# main.net
KiCad netlist of a schematic drawn in Altium Designer
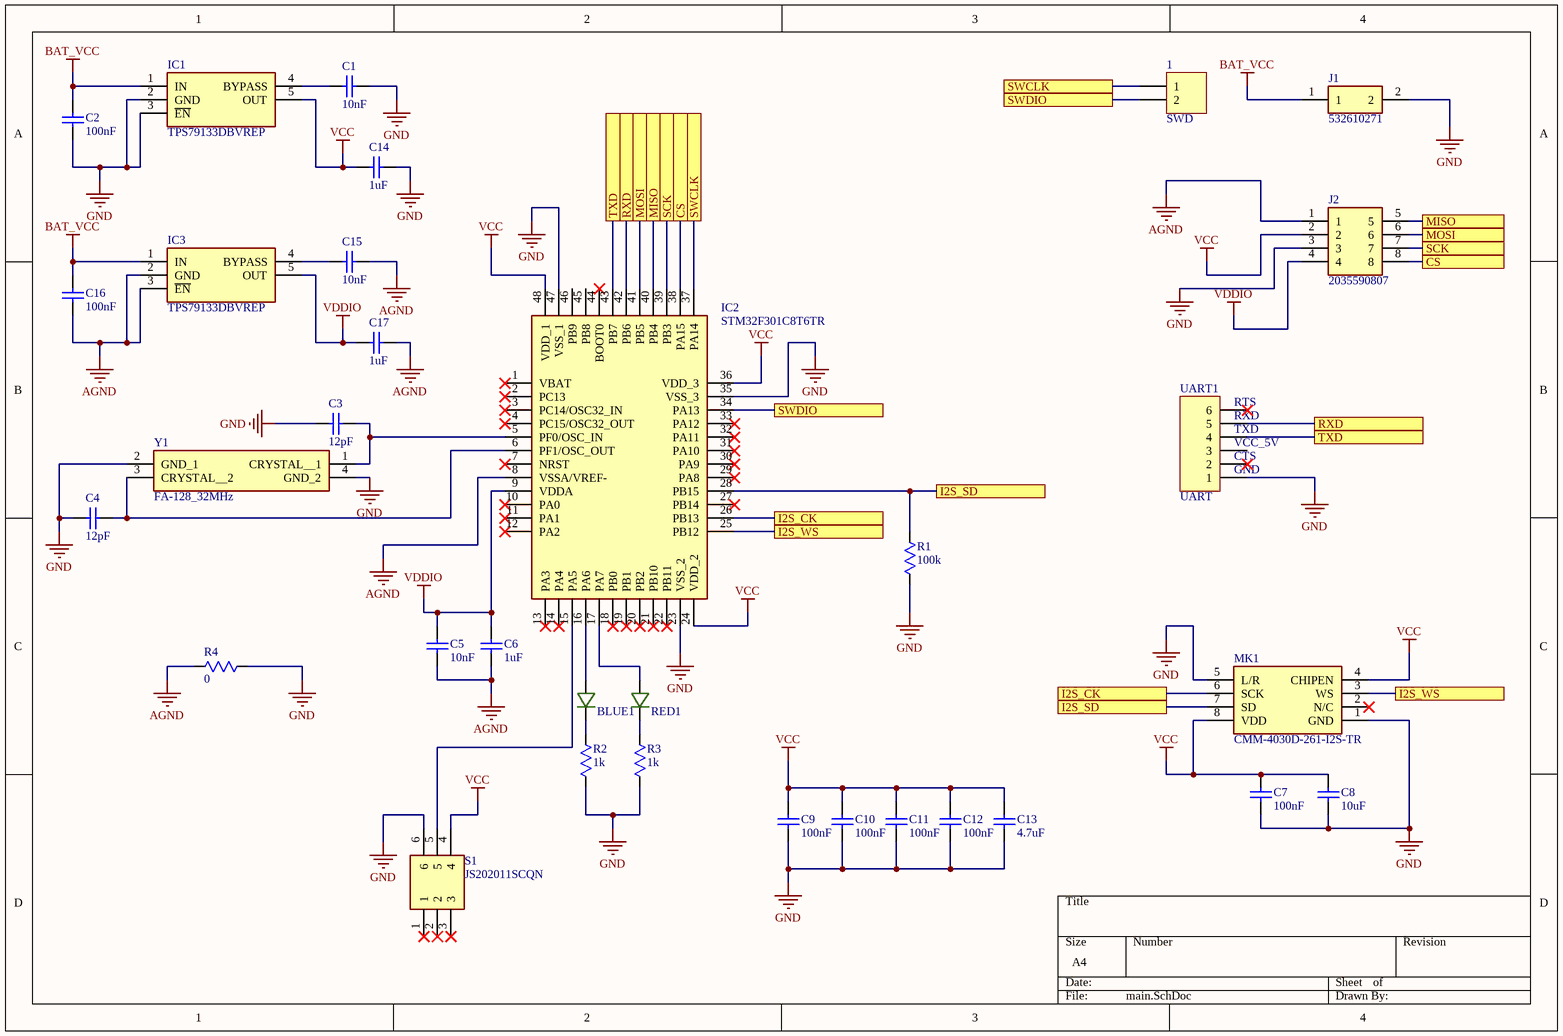
[diagram p0: main.SchDoc]

(export (version "E")
  (design (tool "Eeschema 10.0.6"))
  (components
    (comp (ref "1")
      (value "SWD")
      (footprint "HDR1X2")
      (description "Header, 2-Pin")
      (fields (field (name "PUBLISHER") "Altium Limited"))
      (libsource (lib "Miscellaneous Connectors") (part "Header 2"))
    )
    (comp (ref "BLUE1")
      (value "LG_L29K")
      (footprint "OSRAM LG L29K")
      (description "LED Uni-Color Green 572nm 2-Pin Chip 0603(1608Metric) T/R")
      (libsource (lib "Wearable components") (part "LG_L29K"))
    )
    (comp (ref "C1")
      (value "10nF")
      (footprint "CAP_2012")
      (description "2012(Metric) smd ceramic capacitor")
      (fields (field (name "TOLERANCE") "80%"))
      (libsource (lib "smd componenets") (part "CAP 2012"))
    )
    (comp (ref "C2")
      (value "100nF")
      (footprint "CAP_2012")
      (description "2012(Metric) smd ceramic capacitor")
      (fields (field (name "TOLERANCE") "80%"))
      (libsource (lib "smd componenets") (part "CAP 2012"))
    )
    (comp (ref "C3")
      (value "12pF")
      (footprint "CAP_2012")
      (description "2012(Metric) smd ceramic capacitor")
      (fields (field (name "TOLERANCE") "80%"))
      (libsource (lib "smd componenets") (part "CAP 2012"))
    )
    (comp (ref "C4")
      (value "12pF")
      (footprint "CAP_2012")
      (description "2012(Metric) smd ceramic capacitor")
      (fields (field (name "TOLERANCE") "80%"))
      (libsource (lib "smd componenets") (part "CAP 2012"))
    )
    (comp (ref "C5")
      (value "10nF")
      (footprint "CAP_2012")
      (description "2012(Metric) smd ceramic capacitor")
      (fields (field (name "TOLERANCE") "80%"))
      (libsource (lib "smd componenets") (part "CAP 2012"))
    )
    (comp (ref "C6")
      (value "1uF")
      (footprint "CAP_2012")
      (description "2012(Metric) smd ceramic capacitor")
      (fields (field (name "TOLERANCE") "80%"))
      (libsource (lib "smd componenets") (part "CAP 2012"))
    )
    (comp (ref "C7")
      (value "100nF")
      (footprint "CAP_2012")
      (description "2012(Metric) smd ceramic capacitor")
      (fields (field (name "TOLERANCE") "80%"))
      (libsource (lib "smd componenets") (part "CAP 2012"))
    )
    (comp (ref "C8")
      (value "10uF")
      (footprint "CAP_2012")
      (description "2012(Metric) smd ceramic capacitor")
      (fields (field (name "TOLERANCE") "80%"))
      (libsource (lib "smd componenets") (part "CAP 2012"))
    )
    (comp (ref "C9")
      (value "100nF")
      (footprint "CAP_2012")
      (description "2012(Metric) smd ceramic capacitor")
      (fields (field (name "TOLERANCE") "80%"))
      (libsource (lib "smd componenets") (part "CAP 2012"))
    )
    (comp (ref "C10")
      (value "100nF")
      (footprint "CAP_2012")
      (description "2012(Metric) smd ceramic capacitor")
      (fields (field (name "TOLERANCE") "80%"))
      (libsource (lib "smd componenets") (part "CAP 2012"))
    )
    (comp (ref "C11")
      (value "100nF")
      (footprint "CAP_2012")
      (description "2012(Metric) smd ceramic capacitor")
      (fields (field (name "TOLERANCE") "80%"))
      (libsource (lib "smd componenets") (part "CAP 2012"))
    )
    (comp (ref "C12")
      (value "100nF")
      (footprint "CAP_2012")
      (description "2012(Metric) smd ceramic capacitor")
      (fields (field (name "TOLERANCE") "80%"))
      (libsource (lib "smd componenets") (part "CAP 2012"))
    )
    (comp (ref "C13")
      (value "4.7uF")
      (footprint "CAP_2012")
      (description "2012(Metric) smd ceramic capacitor")
      (fields (field (name "TOLERANCE") "80%"))
      (libsource (lib "smd componenets") (part "CAP 2012"))
    )
    (comp (ref "C14")
      (value "1uF")
      (footprint "CAP_2012")
      (description "2012(Metric) smd ceramic capacitor")
      (fields (field (name "TOLERANCE") "80%"))
      (libsource (lib "smd componenets") (part "CAP 2012"))
    )
    (comp (ref "C15")
      (value "10nF")
      (footprint "CAP_2012")
      (description "2012(Metric) smd ceramic capacitor")
      (fields (field (name "TOLERANCE") "80%"))
      (libsource (lib "smd componenets") (part "CAP 2012"))
    )
    (comp (ref "C16")
      (value "100nF")
      (footprint "CAP_2012")
      (description "2012(Metric) smd ceramic capacitor")
      (fields (field (name "TOLERANCE") "80%"))
      (libsource (lib "smd componenets") (part "CAP 2012"))
    )
    (comp (ref "C17")
      (value "1uF")
      (footprint "CAP_2012")
      (description "2012(Metric) smd ceramic capacitor")
      (fields (field (name "TOLERANCE") "80%"))
      (libsource (lib "smd componenets") (part "CAP 2012"))
    )
    (comp (ref "IC1")
      (value "TPS79133DBVREP")
      (footprint "SamacSys:SOT95P280X145-5N")
      (description "Integrated Circuit")
      (fields (field (name "MOUSER PART NUMBER") "595-TPS79133DBVREP"))
      (libsource (lib "*") (part "TPS79133DBVREP"))
    )
    (comp (ref "IC2")
      (value "STM32F301C8T6TR")
      (footprint "SamacSys:QFP50P900X900X160-48N")
      (description "Integrated Circuit")
      (fields (field (name "MOUSER PART NUMBER") "511-STM32F301C8T6TR"))
      (libsource (lib "SamacSys") (part "STM32F301C8T6TR"))
    )
    (comp (ref "IC3")
      (value "TPS79133DBVREP")
      (footprint "SamacSys:SOT95P280X145-5N")
      (description "Integrated Circuit")
      (fields (field (name "MOUSER PART NUMBER") "595-TPS79133DBVREP"))
      (libsource (lib "*") (part "TPS79133DBVREP"))
    )
    (comp (ref "J1")
      (value "532610271")
      (footprint "SamacSys:532610271")
      (description "Connector")
      (libsource (lib "SamacSys") (part "532610271"))
    )
    (comp (ref "J2")
      (value "2035590807")
      (footprint "SamacSys:2035590807")
      (description "Connector")
      (libsource (lib "*") (part "2035590807"))
    )
    (comp (ref "MK1")
      (value "CMM-4030D-261-I2S-TR")
      (footprint "SamacSys:CMM4030D261I2STR")
      (description "Microphone")
      (fields (field (name "MOUSER PART NUMBER") "490-CMM4030D261I2STR"))
      (libsource (lib "SamacSys") (part "CMM-4030D-261-I2S-TR"))
    )
    (comp (ref "R1")
      (value "100k")
      (footprint "RES_2012")
      (description "2012(Metric) smd resistor")
      (fields
        (field (name "MANUFACTURER_PART_NUMBER") "WR08X000 PTL")
        (field (name "TOLERANCE") "1%")
        (field (name "COPYRIGHT") "Copyright (C) 2016 Accelerated Designs. All rights reserved")
      )
      (libsource (lib "smd componenets") (part "RES 2012"))
    )
    (comp (ref "R2")
      (value "1k")
      (footprint "RES_2012")
      (description "2012(Metric) smd resistor")
      (fields
        (field (name "MANUFACTURER_PART_NUMBER") "WR08X000 PTL")
        (field (name "TOLERANCE") "1%")
        (field (name "COPYRIGHT") "Copyright (C) 2016 Accelerated Designs. All rights reserved")
      )
      (libsource (lib "smd componenets") (part "RES 2012"))
    )
    (comp (ref "R3")
      (value "1k")
      (footprint "RES_2012")
      (description "2012(Metric) smd resistor")
      (fields
        (field (name "MANUFACTURER_PART_NUMBER") "WR08X000 PTL")
        (field (name "TOLERANCE") "1%")
        (field (name "COPYRIGHT") "Copyright (C) 2016 Accelerated Designs. All rights reserved")
      )
      (libsource (lib "smd componenets") (part "RES 2012"))
    )
    (comp (ref "R4")
      (value "0")
      (footprint "RES_2012")
      (description "2012(Metric) smd resistor")
      (fields
        (field (name "MANUFACTURER_PART_NUMBER") "WR08X000 PTL")
        (field (name "TOLERANCE") "1%")
        (field (name "COPYRIGHT") "Copyright (C) 2016 Accelerated Designs. All rights reserved")
      )
      (libsource (lib "smd componenets") (part "RES 2012"))
    )
    (comp (ref "RED1")
      (value "LG_L29K")
      (footprint "OSRAM LG L29K")
      (description "LED Uni-Color Green 572nm 2-Pin Chip 0603(1608Metric) T/R")
      (libsource (lib "Wearable components") (part "LG_L29K"))
    )
    (comp (ref "S1")
      (value "JS202011SCQN")
      (footprint "SamacSys:JS202011SCQN")
      (description "Switch")
      (fields (field (name "MOUSER PART NUMBER") "611-JS202011SCQN"))
      (libsource (lib "*") (part "JS202011SCQN"))
    )
    (comp (ref "UART1")
      (value "UART")
      (footprint "HDR1X6")
      (description "Header, 6-Pin")
      (fields (field (name "PUBLISHER") "Altium Limited"))
      (libsource (lib "Miscellaneous Connectors") (part "Header 6"))
    )
    (comp (ref "Y1")
      (value "FA-128_32MHz")
      (footprint "SamacSys:FA128480000MF20XK")
      (description "Crystal or Oscillator")
      (fields
        (field (name "MANUFACTURER_PART_NUMBER") "FA-128 48.0000MF20X-K")
        (field (name "MOUSER PART NUMBER") "732-FA-12848F20X-K")
      )
      (libsource (lib "*") (part "FA-128_48.0000MF20X-K"))
    )
  )
  (nets
    (net (code "1") (name "/CS") (class "Default")
      (node (ref "IC2") (pin "38") (pinfunction "PA15_38") (pintype "passive"))
      (node (ref "J2") (pin "8") (pinfunction "8_8") (pintype "passive"))
    )
    (net (code "2") (name "/I2S_CK") (class "Default")
      (node (ref "IC2") (pin "26") (pinfunction "PB13_26") (pintype "passive"))
      (node (ref "MK1") (pin "6") (pinfunction "SCK_6") (pintype "passive"))
    )
    (net (code "3") (name "/I2S_SD") (class "Default")
      (node (ref "IC2") (pin "28") (pinfunction "PB15_28") (pintype "passive"))
      (node (ref "MK1") (pin "7") (pinfunction "SD_7") (pintype "passive"))
      (node (ref "R1") (pin "2") (pinfunction "2_2") (pintype "passive"))
    )
    (net (code "4") (name "/I2S_WS") (class "Default")
      (node (ref "IC2") (pin "25") (pinfunction "PB12_25") (pintype "passive"))
      (node (ref "MK1") (pin "3") (pinfunction "WS_3") (pintype "passive"))
    )
    (net (code "5") (name "/MISO") (class "Default")
      (node (ref "IC2") (pin "40") (pinfunction "PB4_40") (pintype "passive"))
      (node (ref "J2") (pin "5") (pinfunction "5_5") (pintype "passive"))
    )
    (net (code "6") (name "/MOSI") (class "Default")
      (node (ref "IC2") (pin "41") (pinfunction "PB5_41") (pintype "passive"))
      (node (ref "J2") (pin "6") (pinfunction "6_6") (pintype "passive"))
    )
    (net (code "7") (name "/RXD") (class "Default")
      (node (ref "IC2") (pin "42") (pinfunction "PB6_42") (pintype "passive"))
      (node (ref "UART1") (pin "5") (pinfunction "5_5") (pintype "passive"))
    )
    (net (code "8") (name "/SCK") (class "Default")
      (node (ref "IC2") (pin "39") (pinfunction "PB3_39") (pintype "passive"))
      (node (ref "J2") (pin "7") (pinfunction "7_7") (pintype "passive"))
    )
    (net (code "9") (name "/SWCLK") (class "Default")
      (node (ref "1") (pin "1") (pinfunction "1_1") (pintype "passive"))
      (node (ref "IC2") (pin "37") (pinfunction "PA14_37") (pintype "passive"))
    )
    (net (code "10") (name "/SWDIO") (class "Default")
      (node (ref "1") (pin "2") (pinfunction "2_2") (pintype "passive"))
      (node (ref "IC2") (pin "34") (pinfunction "PA13_34") (pintype "passive"))
    )
    (net (code "11") (name "/TXD") (class "Default")
      (node (ref "IC2") (pin "43") (pinfunction "PB7_43") (pintype "passive"))
      (node (ref "UART1") (pin "4") (pinfunction "4_4") (pintype "passive"))
    )
    (net (code "12") (name "AGND") (class "Default")
      (node (ref "C15") (pin "1") (pinfunction "1_1") (pintype "passive"))
      (node (ref "C16") (pin "1") (pinfunction "1_1") (pintype "passive"))
      (node (ref "C17") (pin "1") (pinfunction "1_1") (pintype "passive"))
      (node (ref "C5") (pin "1") (pinfunction "1_1") (pintype "passive"))
      (node (ref "C6") (pin "1") (pinfunction "1_1") (pintype "passive"))
      (node (ref "IC2") (pin "8") (pinfunction "VSSA/VREF-_8") (pintype "passive"))
      (node (ref "IC3") (pin "2") (pinfunction "GND_2") (pintype "passive"))
      (node (ref "IC3") (pin "3") (pinfunction "~{EN}_3") (pintype "passive"))
      (node (ref "J2") (pin "1") (pinfunction "1_1") (pintype "passive"))
      (node (ref "R4") (pin "2") (pinfunction "2_2") (pintype "passive"))
    )
    (net (code "13") (name "BAT_VCC") (class "Default")
      (node (ref "C16") (pin "2") (pinfunction "2_2") (pintype "passive"))
      (node (ref "C2") (pin "2") (pinfunction "2_2") (pintype "passive"))
      (node (ref "IC1") (pin "1") (pinfunction "IN_1") (pintype "passive"))
      (node (ref "IC3") (pin "1") (pinfunction "IN_1") (pintype "passive"))
      (node (ref "J1") (pin "1") (pinfunction "1_1") (pintype "passive"))
    )
    (net (code "14") (name "GND") (class "Default")
      (node (ref "C1") (pin "1") (pinfunction "1_1") (pintype "passive"))
      (node (ref "C10") (pin "1") (pinfunction "1_1") (pintype "passive"))
      (node (ref "C11") (pin "1") (pinfunction "1_1") (pintype "passive"))
      (node (ref "C12") (pin "1") (pinfunction "1_1") (pintype "passive"))
      (node (ref "C13") (pin "1") (pinfunction "1_1") (pintype "passive"))
      (node (ref "C14") (pin "1") (pinfunction "1_1") (pintype "passive"))
      (node (ref "C2") (pin "1") (pinfunction "1_1") (pintype "passive"))
      (node (ref "C3") (pin "2") (pinfunction "2_2") (pintype "passive"))
      (node (ref "C4") (pin "2") (pinfunction "2_2") (pintype "passive"))
      (node (ref "C7") (pin "1") (pinfunction "1_1") (pintype "passive"))
      (node (ref "C8") (pin "1") (pinfunction "1_1") (pintype "passive"))
      (node (ref "C9") (pin "1") (pinfunction "1_1") (pintype "passive"))
      (node (ref "IC1") (pin "2") (pinfunction "GND_2") (pintype "passive"))
      (node (ref "IC1") (pin "3") (pinfunction "~{EN}_3") (pintype "passive"))
      (node (ref "IC2") (pin "23") (pinfunction "VSS_2_23") (pintype "passive"))
      (node (ref "IC2") (pin "35") (pinfunction "VSS_3_35") (pintype "passive"))
      (node (ref "IC2") (pin "47") (pinfunction "VSS_1_47") (pintype "passive"))
      (node (ref "J1") (pin "2") (pinfunction "2_2") (pintype "passive"))
      (node (ref "J2") (pin "3") (pinfunction "3_3") (pintype "passive"))
      (node (ref "MK1") (pin "1") (pinfunction "GND_1") (pintype "passive"))
      (node (ref "MK1") (pin "5") (pinfunction "L/R_5") (pintype "passive"))
      (node (ref "R1") (pin "1") (pinfunction "1_1") (pintype "passive"))
      (node (ref "R2") (pin "1") (pinfunction "1_1") (pintype "passive"))
      (node (ref "R3") (pin "1") (pinfunction "1_1") (pintype "passive"))
      (node (ref "R4") (pin "1") (pinfunction "1_1") (pintype "passive"))
      (node (ref "S1") (pin "6") (pinfunction "6_6") (pintype "passive"))
      (node (ref "UART1") (pin "1") (pinfunction "1_1") (pintype "passive"))
      (node (ref "Y1") (pin "2") (pinfunction "GND_1_2") (pintype "passive"))
      (node (ref "Y1") (pin "4") (pinfunction "GND_2_4") (pintype "passive"))
    )
    (net (code "15") (name "Net-(BLUE1-A)") (class "Default")
      (node (ref "BLUE1") (pin "2") (pinfunction "A_2") (pintype "passive"))
      (node (ref "IC2") (pin "16") (pinfunction "PA6_16") (pintype "passive"))
    )
    (net (code "16") (name "Net-(BLUE1-C)") (class "Default")
      (node (ref "BLUE1") (pin "1") (pinfunction "C_1") (pintype "passive"))
      (node (ref "R2") (pin "2") (pinfunction "2_2") (pintype "passive"))
    )
    (net (code "17") (name "Net-(IC1-BYPASS)") (class "Default")
      (node (ref "C1") (pin "2") (pinfunction "2_2") (pintype "passive"))
      (node (ref "IC1") (pin "4") (pinfunction "BYPASS_4") (pintype "passive"))
    )
    (net (code "18") (name "Net-(IC2-PA5)") (class "Default")
      (node (ref "IC2") (pin "15") (pinfunction "PA5_15") (pintype "passive"))
      (node (ref "S1") (pin "5") (pinfunction "5_5") (pintype "passive"))
    )
    (net (code "19") (name "Net-(IC2-PA7)") (class "Default")
      (node (ref "IC2") (pin "17") (pinfunction "PA7_17") (pintype "passive"))
      (node (ref "RED1") (pin "2") (pinfunction "A_2") (pintype "passive"))
    )
    (net (code "20") (name "Net-(IC2-PF0{slash}OSC_IN)") (class "Default")
      (node (ref "C3") (pin "1") (pinfunction "1_1") (pintype "passive"))
      (node (ref "IC2") (pin "5") (pinfunction "PF0/OSC_IN_5") (pintype "passive"))
      (node (ref "Y1") (pin "1") (pinfunction "CRYSTAL__1_1") (pintype "passive"))
    )
    (net (code "21") (name "Net-(IC2-PF1{slash}OSC_OUT)") (class "Default")
      (node (ref "C4") (pin "1") (pinfunction "1_1") (pintype "passive"))
      (node (ref "IC2") (pin "6") (pinfunction "PF1/OSC_OUT_6") (pintype "passive"))
      (node (ref "Y1") (pin "3") (pinfunction "CRYSTAL__2_3") (pintype "passive"))
    )
    (net (code "22") (name "Net-(IC3-BYPASS)") (class "Default")
      (node (ref "C15") (pin "2") (pinfunction "2_2") (pintype "passive"))
      (node (ref "IC3") (pin "4") (pinfunction "BYPASS_4") (pintype "passive"))
    )
    (net (code "23") (name "Net-(RED1-C)") (class "Default")
      (node (ref "R3") (pin "2") (pinfunction "2_2") (pintype "passive"))
      (node (ref "RED1") (pin "1") (pinfunction "C_1") (pintype "passive"))
    )
    (net (code "24") (name "VCC") (class "Default")
      (node (ref "C10") (pin "2") (pinfunction "2_2") (pintype "passive"))
      (node (ref "C11") (pin "2") (pinfunction "2_2") (pintype "passive"))
      (node (ref "C12") (pin "2") (pinfunction "2_2") (pintype "passive"))
      (node (ref "C13") (pin "2") (pinfunction "2_2") (pintype "passive"))
      (node (ref "C14") (pin "2") (pinfunction "2_2") (pintype "passive"))
      (node (ref "C7") (pin "2") (pinfunction "2_2") (pintype "passive"))
      (node (ref "C8") (pin "2") (pinfunction "2_2") (pintype "passive"))
      (node (ref "C9") (pin "2") (pinfunction "2_2") (pintype "passive"))
      (node (ref "IC1") (pin "5") (pinfunction "OUT_5") (pintype "passive"))
      (node (ref "IC2") (pin "24") (pinfunction "VDD_2_24") (pintype "passive"))
      (node (ref "IC2") (pin "36") (pinfunction "VDD_3_36") (pintype "passive"))
      (node (ref "IC2") (pin "48") (pinfunction "VDD_1_48") (pintype "passive"))
      (node (ref "J2") (pin "2") (pinfunction "2_2") (pintype "passive"))
      (node (ref "MK1") (pin "4") (pinfunction "CHIPEN_4") (pintype "passive"))
      (node (ref "MK1") (pin "8") (pinfunction "VDD_8") (pintype "passive"))
      (node (ref "S1") (pin "4") (pinfunction "4_4") (pintype "passive"))
    )
    (net (code "25") (name "VDDIO") (class "Default")
      (node (ref "C17") (pin "2") (pinfunction "2_2") (pintype "passive"))
      (node (ref "C5") (pin "2") (pinfunction "2_2") (pintype "passive"))
      (node (ref "C6") (pin "2") (pinfunction "2_2") (pintype "passive"))
      (node (ref "IC2") (pin "9") (pinfunction "VDDA_9") (pintype "passive"))
      (node (ref "IC3") (pin "5") (pinfunction "OUT_5") (pintype "passive"))
      (node (ref "J2") (pin "4") (pinfunction "4_4") (pintype "passive"))
    )
    (net (code "26") (name "unconnected-(IC2-BOOT0-Pad44)") (class "Default")
      (node (ref "IC2") (pin "44") (pinfunction "BOOT0_44") (pintype "passive+no_connect"))
    )
    (net (code "27") (name "unconnected-(IC2-NRST-Pad7)") (class "Default")
      (node (ref "IC2") (pin "7") (pinfunction "NRST_7") (pintype "passive+no_connect"))
    )
    (net (code "28") (name "unconnected-(IC2-PA0-Pad10)") (class "Default")
      (node (ref "IC2") (pin "10") (pinfunction "PA0_10") (pintype "passive+no_connect"))
    )
    (net (code "29") (name "unconnected-(IC2-PA1-Pad11)") (class "Default")
      (node (ref "IC2") (pin "11") (pinfunction "PA1_11") (pintype "passive+no_connect"))
    )
    (net (code "30") (name "unconnected-(IC2-PA2-Pad12)") (class "Default")
      (node (ref "IC2") (pin "12") (pinfunction "PA2_12") (pintype "passive+no_connect"))
    )
    (net (code "31") (name "unconnected-(IC2-PA3-Pad13)") (class "Default")
      (node (ref "IC2") (pin "13") (pinfunction "PA3_13") (pintype "passive+no_connect"))
    )
    (net (code "32") (name "unconnected-(IC2-PA4-Pad14)") (class "Default")
      (node (ref "IC2") (pin "14") (pinfunction "PA4_14") (pintype "passive+no_connect"))
    )
    (net (code "33") (name "unconnected-(IC2-PA8-Pad29)") (class "Default")
      (node (ref "IC2") (pin "29") (pinfunction "PA8_29") (pintype "passive+no_connect"))
    )
    (net (code "34") (name "unconnected-(IC2-PA9-Pad30)") (class "Default")
      (node (ref "IC2") (pin "30") (pinfunction "PA9_30") (pintype "passive+no_connect"))
    )
    (net (code "35") (name "unconnected-(IC2-PA10-Pad31)") (class "Default")
      (node (ref "IC2") (pin "31") (pinfunction "PA10_31") (pintype "passive+no_connect"))
    )
    (net (code "36") (name "unconnected-(IC2-PA11-Pad32)") (class "Default")
      (node (ref "IC2") (pin "32") (pinfunction "PA11_32") (pintype "passive+no_connect"))
    )
    (net (code "37") (name "unconnected-(IC2-PA12-Pad33)") (class "Default")
      (node (ref "IC2") (pin "33") (pinfunction "PA12_33") (pintype "passive+no_connect"))
    )
    (net (code "38") (name "unconnected-(IC2-PB0-Pad18)") (class "Default")
      (node (ref "IC2") (pin "18") (pinfunction "PB0_18") (pintype "passive+no_connect"))
    )
    (net (code "39") (name "unconnected-(IC2-PB1-Pad19)") (class "Default")
      (node (ref "IC2") (pin "19") (pinfunction "PB1_19") (pintype "passive+no_connect"))
    )
    (net (code "40") (name "unconnected-(IC2-PB2-Pad20)") (class "Default")
      (node (ref "IC2") (pin "20") (pinfunction "PB2_20") (pintype "passive+no_connect"))
    )
    (net (code "41") (name "unconnected-(IC2-PB8-Pad45)") (class "Default")
      (node (ref "IC2") (pin "45") (pinfunction "PB8_45") (pintype "passive"))
    )
    (net (code "42") (name "unconnected-(IC2-PB9-Pad46)") (class "Default")
      (node (ref "IC2") (pin "46") (pinfunction "PB9_46") (pintype "passive"))
    )
    (net (code "43") (name "unconnected-(IC2-PB10-Pad21)") (class "Default")
      (node (ref "IC2") (pin "21") (pinfunction "PB10_21") (pintype "passive+no_connect"))
    )
    (net (code "44") (name "unconnected-(IC2-PB11-Pad22)") (class "Default")
      (node (ref "IC2") (pin "22") (pinfunction "PB11_22") (pintype "passive+no_connect"))
    )
    (net (code "45") (name "unconnected-(IC2-PB14-Pad27)") (class "Default")
      (node (ref "IC2") (pin "27") (pinfunction "PB14_27") (pintype "passive+no_connect"))
    )
    (net (code "46") (name "unconnected-(IC2-PC13-Pad2)") (class "Default")
      (node (ref "IC2") (pin "2") (pinfunction "PC13_2") (pintype "passive+no_connect"))
    )
    (net (code "47") (name "unconnected-(IC2-PC14{slash}OSC32_IN-Pad3)") (class "Default")
      (node (ref "IC2") (pin "3") (pinfunction "PC14/OSC32_IN_3") (pintype "passive+no_connect"))
    )
    (net (code "48") (name "unconnected-(IC2-PC15{slash}OSC32_OUT-Pad4)") (class "Default")
      (node (ref "IC2") (pin "4") (pinfunction "PC15/OSC32_OUT_4") (pintype "passive+no_connect"))
    )
    (net (code "49") (name "unconnected-(IC2-VBAT-Pad1)") (class "Default")
      (node (ref "IC2") (pin "1") (pinfunction "VBAT_1") (pintype "passive+no_connect"))
    )
    (net (code "50") (name "unconnected-(MK1-N{slash}C-Pad2)") (class "Default")
      (node (ref "MK1") (pin "2") (pinfunction "N/C_2") (pintype "passive+no_connect"))
    )
    (net (code "51") (name "unconnected-(S1-Pad1)") (class "Default")
      (node (ref "S1") (pin "1") (pinfunction "1_1") (pintype "passive+no_connect"))
    )
    (net (code "52") (name "unconnected-(S1-Pad2)") (class "Default")
      (node (ref "S1") (pin "2") (pinfunction "2_2") (pintype "passive+no_connect"))
    )
    (net (code "53") (name "unconnected-(S1-Pad3)") (class "Default")
      (node (ref "S1") (pin "3") (pinfunction "3_3") (pintype "passive+no_connect"))
    )
    (net (code "54") (name "unconnected-(UART1-Pad2)") (class "Default")
      (node (ref "UART1") (pin "2") (pinfunction "2_2") (pintype "passive+no_connect"))
    )
    (net (code "55") (name "unconnected-(UART1-Pad3)") (class "Default")
      (node (ref "UART1") (pin "3") (pinfunction "3_3") (pintype "passive"))
    )
    (net (code "56") (name "unconnected-(UART1-Pad6)") (class "Default")
      (node (ref "UART1") (pin "6") (pinfunction "6_6") (pintype "passive+no_connect"))
    )
  )
)
